# TMC5160_BOB_V1_2.net
KiCad netlist of a schematic drawn in Altium Designer
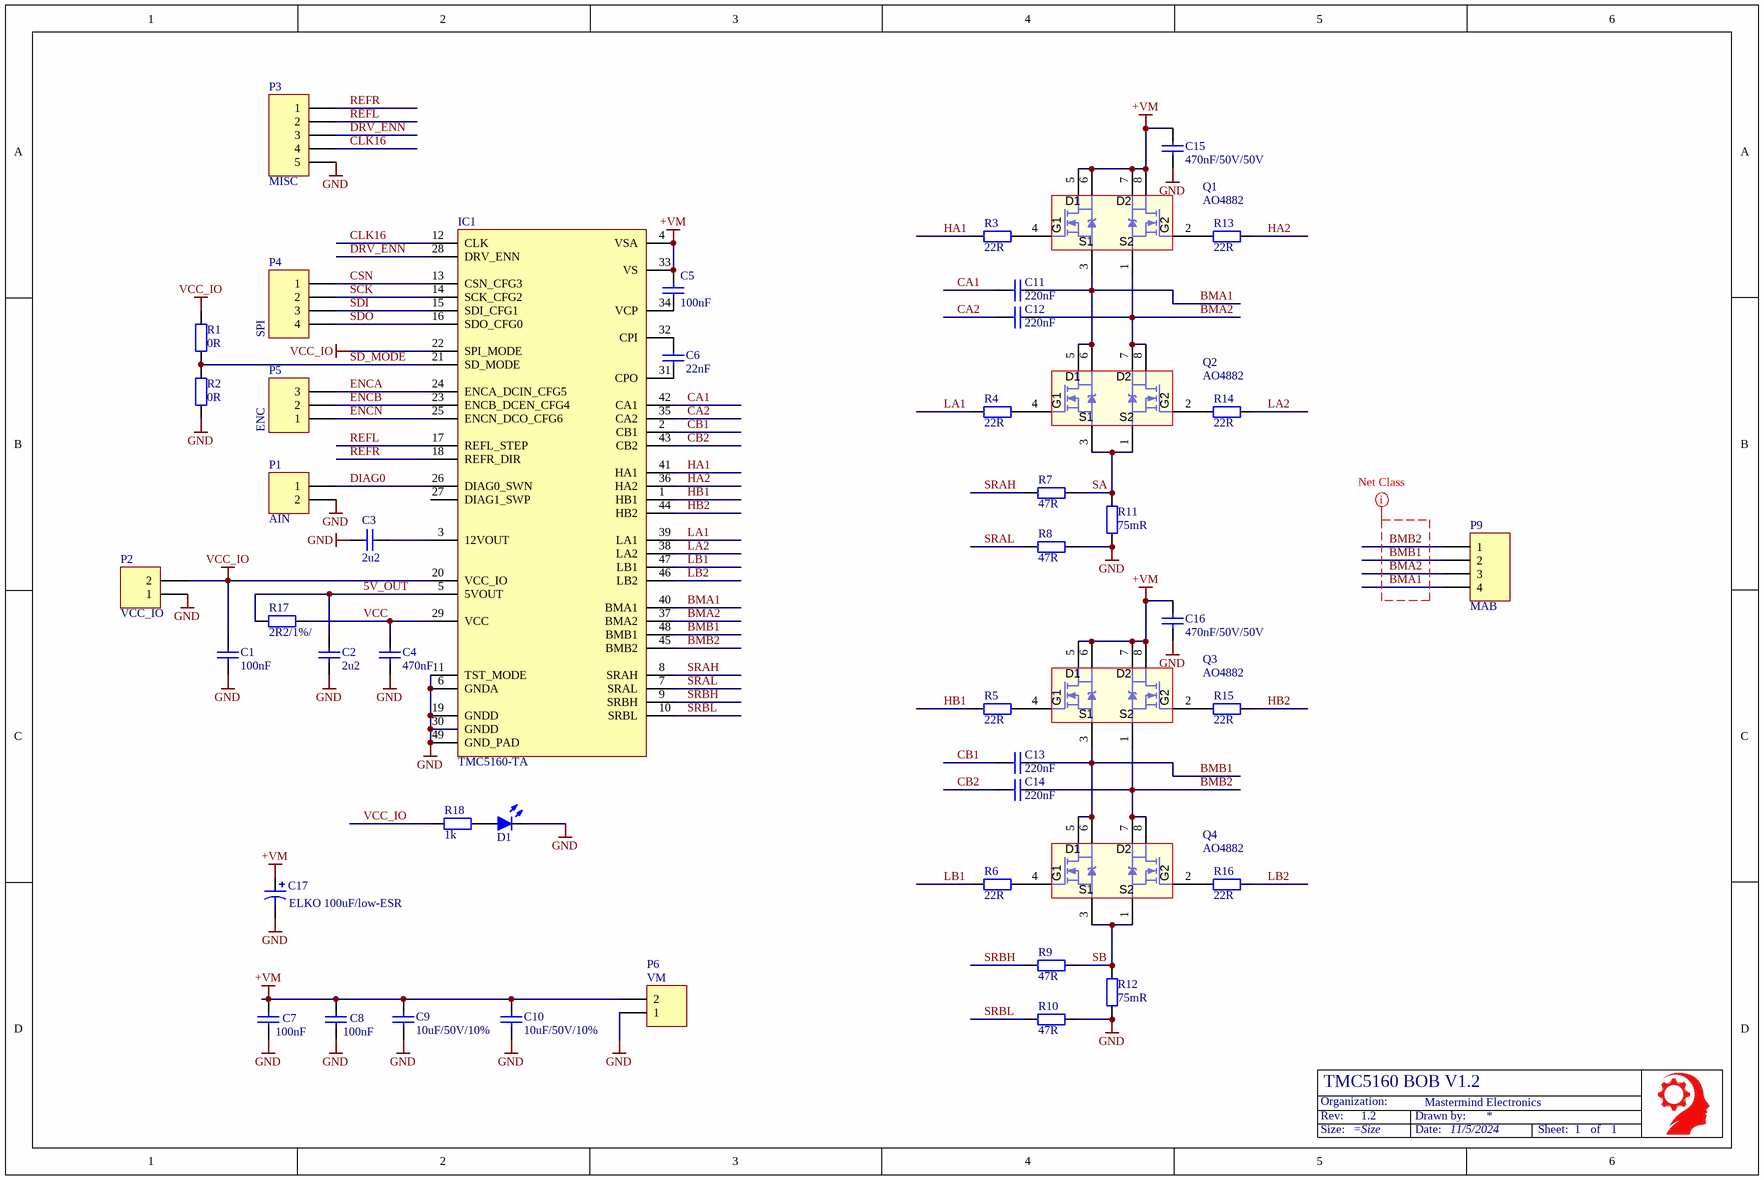
[diagram p0: TMC5160_BOB_V1_2.SchDoc]

(export (version "E")
  (design (tool "Eeschema 10.0.6"))
  (components
    (comp (ref "*")
      (value "TitleBlock")
      (description "Title Block for Schematic Sheets")
      (libsource (lib "mastermind") (part "TitleBlock"))
    )
    (comp (ref "C1")
      (value "100nF")
      (footprint "C0603")
      (description "Ceramic capacitor")
      (fields (field (name "MANUFACTURER") "Multicomp") (field (name "MPN") "MC0603F104M500CT"))
      (libsource (lib "SCH Passives") (part "Capacitor"))
    )
    (comp (ref "C2")
      (value "2u2")
      (footprint "C0603")
      (description "SMD Multilayer Ceramic Capacitor, 0603 [1608 Metric], 2.2 µF, 25 V, ± 10%, X5R, GRM Series")
      (fields (field (name "MF") "MURATA") (field (name "MPN") "GRM188R61E225KA12D"))
      (libsource (lib "TMC5160_RevA") (part "2.2 µF, 25 V, ± 10%, X5R, GRM Series"))
    )
    (comp (ref "C3")
      (value "2u2")
      (footprint "C0603")
      (description "SMD Multilayer Ceramic Capacitor, 0603 [1608 Metric], 2.2 µF, 25 V, ± 10%, X5R, GRM Series")
      (fields (field (name "MF") "MURATA") (field (name "MPN") "GRM188R61E225KA12D"))
      (libsource (lib "TMC5160_RevA") (part "2.2 µF, 25 V, ± 10%, X5R, GRM Series"))
    )
    (comp (ref "C4")
      (value "470nF")
      (footprint "C0603")
      (description "Ceramic capacitor")
      (fields (field (name "MF") "Multicomp") (field (name "MPN") "MC0603X474K160CT"))
      (libsource (lib "SCH Passives") (part "Capacitor"))
    )
    (comp (ref "C5")
      (value "100nF")
      (footprint "C0603")
      (description "Ceramic capacitor")
      (fields (field (name "MF") "Multicomp") (field (name "MPN") "MC0603F104M500CT"))
      (libsource (lib "SCH Passives") (part "Capacitor"))
    )
    (comp (ref "C6")
      (value "22nF")
      (footprint "C0603")
      (description "Ceramic capacitor")
      (fields (field (name "MF") "Multicomp") (field (name "MPN") "MC0603B223K500CT"))
      (libsource (lib "SCH Passives") (part "Capacitor"))
    )
    (comp (ref "C7")
      (value "100nF")
      (footprint "C0603")
      (description "Ceramic capacitor")
      (fields (field (name "MANUFACTURER") "Multicomp") (field (name "MPN") "MC0603F104M500CT"))
      (libsource (lib "SCH Passives") (part "Capacitor"))
    )
    (comp (ref "C8")
      (value "100nF")
      (footprint "C0603")
      (description "Ceramic capacitor")
      (fields (field (name "MANUFACTURER") "Multicomp") (field (name "MPN") "MC0603F104M500CT"))
      (libsource (lib "SCH Passives") (part "Capacitor"))
    )
    (comp (ref "C9")
      (value "10uF/50V/10%")
      (footprint "C1206")
      (description "SMD Multilayer Ceramic Capacitor, 1206 [3216 Metric], 10 µF, 50 V, ± 20%, X5R, GRM Series")
      (fields (field (name "MF") "MURATA") (field (name "MPN") "GRM31CR61H106MA12L"))
      (libsource (lib "TMC262_FDD8424H_RevA") (part "10 µF, 50 V, ± 20%, X5R, GRM Series"))
    )
    (comp (ref "C10")
      (value "10uF/50V/10%")
      (footprint "C1206")
      (description "SMD Multilayer Ceramic Capacitor, 1206 [3216 Metric], 10 µF, 50 V, ± 20%, X5R, GRM Series")
      (fields (field (name "MF") "MURATA") (field (name "MPN") "GRM31CR61H106MA12L"))
      (libsource (lib "TMC262_FDD8424H_RevA") (part "10 µF, 50 V, ± 20%, X5R, GRM Series"))
    )
    (comp (ref "C11")
      (value "220nF")
      (footprint "C0603")
      (description "SMD Multilayer Ceramic Capacitor, 0603 [1608 Metric], 0.22 µF, 50 V, ± 10%, X7R, GCM Series")
      (fields (field (name "MF") "MURATA") (field (name "MPN") "GCM188R71H224KA64D"))
      (libsource (lib "TMC5160_RevA") (part "0.22 µF, 50 V, ± 10%, X7R"))
    )
    (comp (ref "C12")
      (value "220nF")
      (footprint "C0603")
      (description "SMD Multilayer Ceramic Capacitor, 0603 [1608 Metric], 0.22 µF, 50 V, ± 10%, X7R, GCM Series")
      (fields (field (name "MF") "MURATA") (field (name "MPN") "GCM188R71H224KA64D"))
      (libsource (lib "TMC5160_RevA") (part "0.22 µF, 50 V, ± 10%, X7R"))
    )
    (comp (ref "C13")
      (value "220nF")
      (footprint "C0603")
      (description "SMD Multilayer Ceramic Capacitor, 0603 [1608 Metric], 0.22 µF, 50 V, ± 10%, X7R, GCM Series")
      (fields (field (name "MF") "MURATA") (field (name "MPN") "GCM188R71H224KA64D"))
      (libsource (lib "TMC5160_RevA") (part "0.22 µF, 50 V, ± 10%, X7R"))
    )
    (comp (ref "C14")
      (value "220nF")
      (footprint "C0603")
      (description "SMD Multilayer Ceramic Capacitor, 0603 [1608 Metric], 0.22 µF, 50 V, ± 10%, X7R, GCM Series")
      (fields (field (name "MF") "MURATA") (field (name "MPN") "GCM188R71H224KA64D"))
      (libsource (lib "TMC5160_RevA") (part "0.22 µF, 50 V, ± 10%, X7R"))
    )
    (comp (ref "C15")
      (value "470nF/50V/50V")
      (footprint "C0603")
      (description "SMD Multilayer Ceramic Capacitor, 0603 [1608 Metric], 0.47 µF, 50 V, ± 10%, X7R, C Series")
      (fields (field (name "MF") "TDK") (field (name "MPN") "C1608X7R1H474K080AC"))
      (libsource (lib "TMC5160_RevA") (part "0.47 µF, 50 V, ± 10%, X7R, C Series"))
    )
    (comp (ref "C16")
      (value "470nF/50V/50V")
      (footprint "C0603")
      (description "SMD Multilayer Ceramic Capacitor, 0603 [1608 Metric], 0.47 µF, 50 V, ± 10%, X7R, C Series")
      (fields (field (name "MF") "TDK") (field (name "MPN") "C1608X7R1H474K080AC"))
      (libsource (lib "TMC5160_RevA") (part "0.47 µF, 50 V, ± 10%, X7R, C Series"))
    )
    (comp (ref "C17")
      (value "ELKO 100uF/low-ESR")
      (footprint "EXT_POL_CAP")
      (description "Polarized Capacitor (Radial)")
      (fields (field (name "Comment") "Cap Pol1") (field (name "PUBLISHER") "Altium Limited"))
      (libsource (lib "Miscellaneous Devices") (part "Cap Pol1"))
    )
    (comp (ref "D1")
      (value "LED, Blue, SMD, 20mA, 2.8V, 465 nm")
      (footprint "LED_0603")
      (fields (field (name "MF") "Lite-On") (field (name "MPN") "LTST-C191TBKT-5A"))
      (libsource (lib "TMC26x_RevA") (part "LED, Blue, SMD, 20mA, 2.8V, 465 nm"))
    )
    (comp (ref "IC1")
      (value "TMC5160-TA")
      (footprint "TMC5160_TSQFP50P900X900X120_HS-49L")
      (fields (field (name "MANUFACTURER") "TRINAMIC"))
      (libsource (lib "TMC5160_RevA") (part "TMC5160-TA"))
    )
    (comp (ref "P1")
      (value "AIN")
      (footprint "2_PIN_THT")
      (description "Header, 2-Pin")
      (fields (field (name "PUBLISHER") "Altium Limited"))
      (libsource (lib "") (part "Header 2_1"))
    )
    (comp (ref "P2")
      (value "VCC_IO")
      (footprint "2_PIN_THT")
      (description "Header, 2-Pin")
      (fields (field (name "PUBLISHER") "Altium Limited"))
      (libsource (lib "") (part "Header 2_2"))
    )
    (comp (ref "P3")
      (value "MISC")
      (footprint "5_PIN_THT")
      (description "Header, 5-Pin")
      (fields (field (name "PUBLISHER") "Altium Limited"))
      (libsource (lib "Miscellaneous Connectors") (part "Header 5"))
    )
    (comp (ref "P4")
      (value "SPI")
      (footprint "4_PIN_THT")
      (description "Header, 4-Pin")
      (fields (field (name "PUBLISHER") "Altium Limited"))
      (libsource (lib "Miscellaneous Connectors") (part "Header 4"))
    )
    (comp (ref "P5")
      (value "ENC")
      (footprint "3_PIN_THT")
      (description "Header, 3-Pin")
      (fields (field (name "PUBLISHER") "Altium Limited"))
      (libsource (lib "Miscellaneous Connectors") (part "Header 3"))
    )
    (comp (ref "P6")
      (value "VM")
      (footprint "2_PIN_THT")
      (description "Header, 2-Pin")
      (fields (field (name "PUBLISHER") "Altium Limited"))
      (libsource (lib "Miscellaneous Connectors") (part "Header 2"))
    )
    (comp (ref "P9")
      (value "MAB")
      (footprint "4_PIN_THT_1mm_hole")
      (description "Wire-To-Board Connector, 2.5 mm, 4 Contacts, Header, EH Series, Through Hole, 1 Rows")
      (fields (field (name "MPN") "B4B-EH-A") (field (name "MF") "JST (JAPAN SOLDERLESS TERMINALS)"))
      (libsource (lib "TMC5160_RevA") (part "Wire-To-Board Connector, 2.5 mm, 4 Contacts, Header, EH Series, Through Hole, 1 Rows"))
    )
    (comp (ref "Q1")
      (value "AO4882")
      (footprint "SOP127P600X170-8L")
      (description "Mosfet Array 2 N-Channel (Dual) 40V 8A 2W Surface Mount 8-SOIC")
      (fields (field (name "MF") "Alpha & Omega Semiconductor Inc."))
      (libsource (lib "TMC5160_RevA") (part "AO4882 MOSFET 2N-CH 40V 8A 8SOIC"))
    )
    (comp (ref "Q2")
      (value "AO4882")
      (footprint "SOP127P600X170-8L")
      (description "Mosfet Array 2 N-Channel (Dual) 40V 8A 2W Surface Mount 8-SOIC")
      (fields (field (name "MF") "Alpha & Omega Semiconductor Inc."))
      (libsource (lib "TMC5160_RevA") (part "AO4882 MOSFET 2N-CH 40V 8A 8SOIC"))
    )
    (comp (ref "Q3")
      (value "AO4882")
      (footprint "SOP127P600X170-8L")
      (description "Mosfet Array 2 N-Channel (Dual) 40V 8A 2W Surface Mount 8-SOIC")
      (fields (field (name "MF") "Alpha & Omega Semiconductor Inc."))
      (libsource (lib "TMC5160_RevA") (part "AO4882 MOSFET 2N-CH 40V 8A 8SOIC"))
    )
    (comp (ref "Q4")
      (value "AO4882")
      (footprint "SOP127P600X170-8L")
      (description "Mosfet Array 2 N-Channel (Dual) 40V 8A 2W Surface Mount 8-SOIC")
      (fields (field (name "MF") "Alpha & Omega Semiconductor Inc."))
      (libsource (lib "TMC5160_RevA") (part "AO4882 MOSFET 2N-CH 40V 8A 8SOIC"))
    )
    (comp (ref "R1")
      (value "0R")
      (footprint "R0603")
      (description "SMD Chip Resistor, Thick Film, 0 ohm, 0603 [1608 Metric], 100 mW, MCWR Series")
      (fields
        (field (name "MPN") "MCWR06X000 PTL")
        (field (name "MF") "MULTICOMP")
        (field (name "RESISTANCE") "0R")
      )
      (libsource (lib "TMC5160_RevA") (part "0 ohm, 0603 [1608 Metric], 100 mW, MCWR Series"))
    )
    (comp (ref "R2")
      (value "0R")
      (footprint "R0603")
      (description "SMD Chip Resistor, Thick Film, 0 ohm, 0603 [1608 Metric], 100 mW, MCWR Series")
      (fields
        (field (name "MPN") "MCWR06X000 PTL")
        (field (name "MF") "MULTICOMP")
        (field (name "RESISTANCE") "0R")
      )
      (libsource (lib "TMC5160_RevA") (part "0 ohm, 0603 [1608 Metric], 100 mW, MCWR Series"))
    )
    (comp (ref "R3")
      (value "22R / 100mW / 1%")
      (footprint "R0603")
      (description "SMD Chip Resistor, Thick Film, 22 ohm, 50 V, 0603 [1608 Metric], 100 mW, ± 1%, MCWR Series")
      (fields
        (field (name "MPN") "MCWR06X22R0FTLV")
        (field (name "MF") "MULTICOMP")
        (field (name "RESISTANCE") "22R")
      )
      (libsource (lib "TMC5160_RevA") (part "22 ohm, 50 V, 0603 [1608 Metric], 100 mW, ± 1%, MCWR Series"))
    )
    (comp (ref "R4")
      (value "22R / 100mW / 1%")
      (footprint "R0603")
      (description "SMD Chip Resistor, Thick Film, 22 ohm, 50 V, 0603 [1608 Metric], 100 mW, ± 1%, MCWR Series")
      (fields
        (field (name "MPN") "MCWR06X22R0FTLV")
        (field (name "MF") "MULTICOMP")
        (field (name "RESISTANCE") "22R")
      )
      (libsource (lib "TMC5160_RevA") (part "22 ohm, 50 V, 0603 [1608 Metric], 100 mW, ± 1%, MCWR Series"))
    )
    (comp (ref "R5")
      (value "22R / 100mW / 1%")
      (footprint "R0603")
      (description "SMD Chip Resistor, Thick Film, 22 ohm, 50 V, 0603 [1608 Metric], 100 mW, ± 1%, MCWR Series")
      (fields
        (field (name "MPN") "MCWR06X22R0FTLV")
        (field (name "MF") "MULTICOMP")
        (field (name "RESISTANCE") "22R")
      )
      (libsource (lib "TMC5160_RevA") (part "22 ohm, 50 V, 0603 [1608 Metric], 100 mW, ± 1%, MCWR Series"))
    )
    (comp (ref "R6")
      (value "22R / 100mW / 1%")
      (footprint "R0603")
      (description "SMD Chip Resistor, Thick Film, 22 ohm, 50 V, 0603 [1608 Metric], 100 mW, ± 1%, MCWR Series")
      (fields
        (field (name "MPN") "MCWR06X22R0FTLV")
        (field (name "MF") "MULTICOMP")
        (field (name "RESISTANCE") "22R")
      )
      (libsource (lib "TMC5160_RevA") (part "22 ohm, 50 V, 0603 [1608 Metric], 100 mW, ± 1%, MCWR Series"))
    )
    (comp (ref "R7")
      (value "47R /  / 1%")
      (footprint "R0603")
      (description "SMD Chip Resistor, Ceramic, 47 ohm, 75 V, 0603 [1608 Metric], 100 mW, ± 1%, MCSR 06 Series")
      (fields
        (field (name "MPN") "MCSR06X47R0FTL")
        (field (name "MF") "MULTICOMP")
        (field (name "RESISTANCE") "47R")
      )
      (libsource (lib "TMC5160_RevA") (part "47 ohm, 75 V, 0603 [1608 Metric], 100 mW, ± 1%, MCSR 06 Series"))
    )
    (comp (ref "R8")
      (value "47R /  / 1%")
      (footprint "R0603")
      (description "SMD Chip Resistor, Ceramic, 47 ohm, 75 V, 0603 [1608 Metric], 100 mW, ± 1%, MCSR 06 Series")
      (fields
        (field (name "MPN") "MCSR06X47R0FTL")
        (field (name "MF") "MULTICOMP")
        (field (name "RESISTANCE") "47R")
      )
      (libsource (lib "TMC5160_RevA") (part "47 ohm, 75 V, 0603 [1608 Metric], 100 mW, ± 1%, MCSR 06 Series"))
    )
    (comp (ref "R9")
      (value "47R /  / 1%")
      (footprint "R0603")
      (description "SMD Chip Resistor, Ceramic, 47 ohm, 75 V, 0603 [1608 Metric], 100 mW, ± 1%, MCSR 06 Series")
      (fields
        (field (name "MPN") "MCSR06X47R0FTL")
        (field (name "MF") "MULTICOMP")
        (field (name "RESISTANCE") "47R")
      )
      (libsource (lib "TMC5160_RevA") (part "47 ohm, 75 V, 0603 [1608 Metric], 100 mW, ± 1%, MCSR 06 Series"))
    )
    (comp (ref "R10")
      (value "47R /  / 1%")
      (footprint "R0603")
      (description "SMD Chip Resistor, Ceramic, 47 ohm, 75 V, 0603 [1608 Metric], 100 mW, ± 1%, MCSR 06 Series")
      (fields
        (field (name "MPN") "MCSR06X47R0FTL")
        (field (name "MF") "MULTICOMP")
        (field (name "RESISTANCE") "47R")
      )
      (libsource (lib "TMC5160_RevA") (part "47 ohm, 75 V, 0603 [1608 Metric], 100 mW, ± 1%, MCSR 06 Series"))
    )
    (comp (ref "R11")
      (value "75mR")
      (footprint "R1206")
      (description "SMD Chip Resistor, Thick Film, Current Sense Resistors - SMD 1W 0.075ohm 1%")
      (fields
        (field (name "MPN") "ERJ-8BWFR075V")
        (field (name "MF") "Panasonic Electronic Components")
        (field (name "RESISTANCE") "75mR")
      )
      (libsource (lib "SMD_Passives") (part "R_SENS, 0.075 ohm, 1206, 1W, ± 1%, ERJ Series"))
    )
    (comp (ref "R12")
      (value "75mR")
      (footprint "R1206")
      (description "SMD Chip Resistor, Thick Film, Current Sense Resistors - SMD 1W 0.075ohm 1%")
      (fields
        (field (name "MPN") "ERJ-8BWFR075V")
        (field (name "MF") "Panasonic Electronic Components")
        (field (name "RESISTANCE") "75mR")
      )
      (libsource (lib "SMD_Passives") (part "R_SENS, 0.075 ohm, 1206, 1W, ± 1%, ERJ Series"))
    )
    (comp (ref "R13")
      (value "22R / 100mW / 1%")
      (footprint "R0603")
      (description "SMD Chip Resistor, Thick Film, 22 ohm, 50 V, 0603 [1608 Metric], 100 mW, ± 1%, MCWR Series")
      (fields
        (field (name "MPN") "MCWR06X22R0FTLV")
        (field (name "MF") "MULTICOMP")
        (field (name "RESISTANCE") "22R")
      )
      (libsource (lib "TMC5160_RevA") (part "22 ohm, 50 V, 0603 [1608 Metric], 100 mW, ± 1%, MCWR Series"))
    )
    (comp (ref "R14")
      (value "22R / 100mW / 1%")
      (footprint "R0603")
      (description "SMD Chip Resistor, Thick Film, 22 ohm, 50 V, 0603 [1608 Metric], 100 mW, ± 1%, MCWR Series")
      (fields
        (field (name "MPN") "MCWR06X22R0FTLV")
        (field (name "MF") "MULTICOMP")
        (field (name "RESISTANCE") "22R")
      )
      (libsource (lib "TMC5160_RevA") (part "22 ohm, 50 V, 0603 [1608 Metric], 100 mW, ± 1%, MCWR Series"))
    )
    (comp (ref "R15")
      (value "22R / 100mW / 1%")
      (footprint "R0603")
      (description "SMD Chip Resistor, Thick Film, 22 ohm, 50 V, 0603 [1608 Metric], 100 mW, ± 1%, MCWR Series")
      (fields
        (field (name "MPN") "MCWR06X22R0FTLV")
        (field (name "MF") "MULTICOMP")
        (field (name "RESISTANCE") "22R")
      )
      (libsource (lib "TMC5160_RevA") (part "22 ohm, 50 V, 0603 [1608 Metric], 100 mW, ± 1%, MCWR Series"))
    )
    (comp (ref "R16")
      (value "22R / 100mW / 1%")
      (footprint "R0603")
      (description "SMD Chip Resistor, Thick Film, 22 ohm, 50 V, 0603 [1608 Metric], 100 mW, ± 1%, MCWR Series")
      (fields
        (field (name "MPN") "MCWR06X22R0FTLV")
        (field (name "MF") "MULTICOMP")
        (field (name "RESISTANCE") "22R")
      )
      (libsource (lib "TMC5160_RevA") (part "22 ohm, 50 V, 0603 [1608 Metric], 100 mW, ± 1%, MCWR Series"))
    )
    (comp (ref "R17")
      (value "2R2/1%/")
      (footprint "R0603")
      (description "Resistor")
      (fields (field (name "MPN") "MC0063W060312R2") (field (name "MF") "Multicomp"))
      (libsource (lib "SCH Passives") (part "Resistor"))
    )
    (comp (ref "R18")
      (value "1k")
      (footprint "R0603")
      (description "1 kohm, 50 V, 0603 [1608 Metric], 63 mW, ± 1%, MC Series")
      (fields
        (field (name "MPN") "MC0063W060311K")
        (field (name "MF") "MULTICOMP")
        (field (name "RESISTANCE") "1k")
      )
      (libsource (lib "TMC457_RevA") (part "1 kohm, 50 V, 0603 [1608 Metric], 63 mW, ± 1%, MC Series"))
    )
  )
  (nets
    (net (code "1") (name "+VM") (class "Default")
      (node (ref "C10") (pin "2") (pinfunction "2_2") (pintype "passive"))
      (node (ref "C15") (pin "1") (pinfunction "1_1") (pintype "passive"))
      (node (ref "C16") (pin "1") (pinfunction "1_1") (pintype "passive"))
      (node (ref "C17") (pin "1") (pinfunction "1_1") (pintype "passive"))
      (node (ref "C5") (pin "1") (pinfunction "1_1") (pintype "passive"))
      (node (ref "C7") (pin "1") (pinfunction "1_1") (pintype "passive"))
      (node (ref "C8") (pin "1") (pinfunction "1_1") (pintype "passive"))
      (node (ref "C9") (pin "2") (pinfunction "2_2") (pintype "passive"))
      (node (ref "IC1") (pin "33") (pinfunction "VS_33") (pintype "passive"))
      (node (ref "IC1") (pin "4") (pinfunction "VSA_4") (pintype "passive"))
      (node (ref "P6") (pin "2") (pinfunction "2_2") (pintype "passive"))
      (node (ref "Q1") (pin "5") (pinfunction "D1_5") (pintype "passive"))
      (node (ref "Q1") (pin "6") (pinfunction "D1_6") (pintype "passive"))
      (node (ref "Q1") (pin "7") (pinfunction "D2_7") (pintype "passive"))
      (node (ref "Q1") (pin "8") (pinfunction "D2_8") (pintype "passive"))
      (node (ref "Q3") (pin "5") (pinfunction "D1_5") (pintype "passive"))
      (node (ref "Q3") (pin "6") (pinfunction "D1_6") (pintype "passive"))
      (node (ref "Q3") (pin "7") (pinfunction "D2_7") (pintype "passive"))
      (node (ref "Q3") (pin "8") (pinfunction "D2_8") (pintype "passive"))
    )
    (net (code "2") (name "/5V_OUT") (class "Default")
      (node (ref "C2") (pin "1") (pinfunction "1_1") (pintype "passive"))
      (node (ref "IC1") (pin "5") (pinfunction "5VOUT_5") (pintype "passive"))
      (node (ref "R17") (pin "1") (pinfunction "1_1") (pintype "passive"))
    )
    (net (code "3") (name "/BMA1") (class "Default")
      (node (ref "C11") (pin "2") (pinfunction "2_2") (pintype "passive"))
      (node (ref "IC1") (pin "40") (pinfunction "BMA1_40") (pintype "passive"))
      (node (ref "P9") (pin "4") (pinfunction "4_4") (pintype "passive"))
      (node (ref "Q1") (pin "3") (pinfunction "S1_3") (pintype "passive"))
      (node (ref "Q2") (pin "5") (pinfunction "D1_5") (pintype "passive"))
      (node (ref "Q2") (pin "6") (pinfunction "D1_6") (pintype "passive"))
    )
    (net (code "4") (name "/BMA2") (class "Default")
      (node (ref "C12") (pin "2") (pinfunction "2_2") (pintype "passive"))
      (node (ref "IC1") (pin "37") (pinfunction "BMA2_37") (pintype "passive"))
      (node (ref "P9") (pin "3") (pinfunction "3_3") (pintype "passive"))
      (node (ref "Q1") (pin "1") (pinfunction "S2_1") (pintype "passive"))
      (node (ref "Q2") (pin "7") (pinfunction "D2_7") (pintype "passive"))
      (node (ref "Q2") (pin "8") (pinfunction "D2_8") (pintype "passive"))
    )
    (net (code "5") (name "/BMB1") (class "Default")
      (node (ref "C13") (pin "2") (pinfunction "2_2") (pintype "passive"))
      (node (ref "IC1") (pin "48") (pinfunction "BMB1_48") (pintype "passive"))
      (node (ref "P9") (pin "2") (pinfunction "2_2") (pintype "passive"))
      (node (ref "Q3") (pin "3") (pinfunction "S1_3") (pintype "passive"))
      (node (ref "Q4") (pin "5") (pinfunction "D1_5") (pintype "passive"))
      (node (ref "Q4") (pin "6") (pinfunction "D1_6") (pintype "passive"))
    )
    (net (code "6") (name "/BMB2") (class "Default")
      (node (ref "C14") (pin "2") (pinfunction "2_2") (pintype "passive"))
      (node (ref "IC1") (pin "45") (pinfunction "BMB2_45") (pintype "passive"))
      (node (ref "P9") (pin "1") (pinfunction "1_1") (pintype "passive"))
      (node (ref "Q3") (pin "1") (pinfunction "S2_1") (pintype "passive"))
      (node (ref "Q4") (pin "7") (pinfunction "D2_7") (pintype "passive"))
      (node (ref "Q4") (pin "8") (pinfunction "D2_8") (pintype "passive"))
    )
    (net (code "7") (name "/CA1") (class "Default")
      (node (ref "C11") (pin "1") (pinfunction "1_1") (pintype "passive"))
      (node (ref "IC1") (pin "42") (pinfunction "CA1_42") (pintype "passive"))
    )
    (net (code "8") (name "/CA2") (class "Default")
      (node (ref "C12") (pin "1") (pinfunction "1_1") (pintype "passive"))
      (node (ref "IC1") (pin "35") (pinfunction "CA2_35") (pintype "passive"))
    )
    (net (code "9") (name "/CB1") (class "Default")
      (node (ref "C13") (pin "1") (pinfunction "1_1") (pintype "passive"))
      (node (ref "IC1") (pin "2") (pinfunction "CB1_2") (pintype "passive"))
    )
    (net (code "10") (name "/CB2") (class "Default")
      (node (ref "C14") (pin "1") (pinfunction "1_1") (pintype "passive"))
      (node (ref "IC1") (pin "43") (pinfunction "CB2_43") (pintype "passive"))
    )
    (net (code "11") (name "/CLK16") (class "Default")
      (node (ref "IC1") (pin "12") (pinfunction "CLK_12") (pintype "passive"))
      (node (ref "P3") (pin "4") (pinfunction "4_4") (pintype "passive"))
    )
    (net (code "12") (name "/CSN") (class "Default")
      (node (ref "IC1") (pin "13") (pinfunction "CSN_CFG3_13") (pintype "passive"))
      (node (ref "P4") (pin "1") (pinfunction "1_1") (pintype "passive"))
    )
    (net (code "13") (name "/DIAG0") (class "Default")
      (node (ref "IC1") (pin "26") (pinfunction "DIAG0_SWN_26") (pintype "passive"))
      (node (ref "P1") (pin "1") (pinfunction "1_1") (pintype "passive"))
    )
    (net (code "14") (name "/DRV_ENN") (class "Default")
      (node (ref "IC1") (pin "28") (pinfunction "DRV_ENN_28") (pintype "passive"))
      (node (ref "P3") (pin "3") (pinfunction "3_3") (pintype "passive"))
    )
    (net (code "15") (name "/ENCA") (class "Default")
      (node (ref "IC1") (pin "24") (pinfunction "ENCA_DCIN_CFG5_24") (pintype "passive"))
      (node (ref "P5") (pin "3") (pinfunction "3_3") (pintype "passive"))
    )
    (net (code "16") (name "/ENCB") (class "Default")
      (node (ref "IC1") (pin "23") (pinfunction "ENCB_DCEN_CFG4_23") (pintype "passive"))
      (node (ref "P5") (pin "2") (pinfunction "2_2") (pintype "passive"))
    )
    (net (code "17") (name "/ENCN") (class "Default")
      (node (ref "IC1") (pin "25") (pinfunction "ENCN_DCO_CFG6_25") (pintype "passive"))
      (node (ref "P5") (pin "1") (pinfunction "1_1") (pintype "passive"))
    )
    (net (code "18") (name "/HA1") (class "Default")
      (node (ref "IC1") (pin "41") (pinfunction "HA1_41") (pintype "passive"))
      (node (ref "R3") (pin "2") (pinfunction "2_2") (pintype "passive"))
    )
    (net (code "19") (name "/HA2") (class "Default")
      (node (ref "IC1") (pin "36") (pinfunction "HA2_36") (pintype "passive"))
      (node (ref "R13") (pin "1") (pinfunction "1_1") (pintype "passive"))
    )
    (net (code "20") (name "/HB1") (class "Default")
      (node (ref "IC1") (pin "1") (pinfunction "HB1_1") (pintype "passive"))
      (node (ref "R5") (pin "2") (pinfunction "2_2") (pintype "passive"))
    )
    (net (code "21") (name "/HB2") (class "Default")
      (node (ref "IC1") (pin "44") (pinfunction "HB2_44") (pintype "passive"))
      (node (ref "R15") (pin "1") (pinfunction "1_1") (pintype "passive"))
    )
    (net (code "22") (name "/LA1") (class "Default")
      (node (ref "IC1") (pin "39") (pinfunction "LA1_39") (pintype "passive"))
      (node (ref "R4") (pin "2") (pinfunction "2_2") (pintype "passive"))
    )
    (net (code "23") (name "/LA2") (class "Default")
      (node (ref "IC1") (pin "38") (pinfunction "LA2_38") (pintype "passive"))
      (node (ref "R14") (pin "1") (pinfunction "1_1") (pintype "passive"))
    )
    (net (code "24") (name "/LB1") (class "Default")
      (node (ref "IC1") (pin "47") (pinfunction "LB1_47") (pintype "passive"))
      (node (ref "R6") (pin "2") (pinfunction "2_2") (pintype "passive"))
    )
    (net (code "25") (name "/LB2") (class "Default")
      (node (ref "IC1") (pin "46") (pinfunction "LB2_46") (pintype "passive"))
      (node (ref "R16") (pin "1") (pinfunction "1_1") (pintype "passive"))
    )
    (net (code "26") (name "/REFL") (class "Default")
      (node (ref "IC1") (pin "17") (pinfunction "REFL_STEP_17") (pintype "passive"))
      (node (ref "P3") (pin "2") (pinfunction "2_2") (pintype "passive"))
    )
    (net (code "27") (name "/REFR") (class "Default")
      (node (ref "IC1") (pin "18") (pinfunction "REFR_DIR_18") (pintype "passive"))
      (node (ref "P3") (pin "1") (pinfunction "1_1") (pintype "passive"))
    )
    (net (code "28") (name "/SA") (class "Default")
      (node (ref "Q2") (pin "1") (pinfunction "S2_1") (pintype "passive"))
      (node (ref "Q2") (pin "3") (pinfunction "S1_3") (pintype "passive"))
      (node (ref "R11") (pin "1") (pinfunction "1_1") (pintype "passive"))
      (node (ref "R7") (pin "1") (pinfunction "1_1") (pintype "passive"))
    )
    (net (code "29") (name "/SB") (class "Default")
      (node (ref "Q4") (pin "1") (pinfunction "S2_1") (pintype "passive"))
      (node (ref "Q4") (pin "3") (pinfunction "S1_3") (pintype "passive"))
      (node (ref "R12") (pin "1") (pinfunction "1_1") (pintype "passive"))
      (node (ref "R9") (pin "1") (pinfunction "1_1") (pintype "passive"))
    )
    (net (code "30") (name "/SCK") (class "Default")
      (node (ref "IC1") (pin "14") (pinfunction "SCK_CFG2_14") (pintype "passive"))
      (node (ref "P4") (pin "2") (pinfunction "2_2") (pintype "passive"))
    )
    (net (code "31") (name "/SDI") (class "Default")
      (node (ref "IC1") (pin "15") (pinfunction "SDI_CFG1_15") (pintype "passive"))
      (node (ref "P4") (pin "3") (pinfunction "3_3") (pintype "passive"))
    )
    (net (code "32") (name "/SDO") (class "Default")
      (node (ref "IC1") (pin "16") (pinfunction "SDO_CFG0_16") (pintype "passive"))
      (node (ref "P4") (pin "4") (pinfunction "4_4") (pintype "passive"))
    )
    (net (code "33") (name "/SD_MODE") (class "Default")
      (node (ref "IC1") (pin "21") (pinfunction "SD_MODE_21") (pintype "passive"))
      (node (ref "R1") (pin "2") (pinfunction "2_2") (pintype "passive"))
      (node (ref "R2") (pin "1") (pinfunction "1_1") (pintype "passive"))
    )
    (net (code "34") (name "/SRAH") (class "Default")
      (node (ref "IC1") (pin "8") (pinfunction "SRAH_8") (pintype "passive"))
      (node (ref "R7") (pin "2") (pinfunction "2_2") (pintype "passive"))
    )
    (net (code "35") (name "/SRAL") (class "Default")
      (node (ref "IC1") (pin "7") (pinfunction "SRAL_7") (pintype "passive"))
      (node (ref "R8") (pin "2") (pinfunction "2_2") (pintype "passive"))
    )
    (net (code "36") (name "/SRBH") (class "Default")
      (node (ref "IC1") (pin "9") (pinfunction "SRBH_9") (pintype "passive"))
      (node (ref "R9") (pin "2") (pinfunction "2_2") (pintype "passive"))
    )
    (net (code "37") (name "/SRBL") (class "Default")
      (node (ref "IC1") (pin "10") (pinfunction "SRBL_10") (pintype "passive"))
      (node (ref "R10") (pin "2") (pinfunction "2_2") (pintype "passive"))
    )
    (net (code "38") (name "/VCC") (class "Default")
      (node (ref "C4") (pin "1") (pinfunction "1_1") (pintype "passive"))
      (node (ref "IC1") (pin "29") (pinfunction "VCC_29") (pintype "passive"))
      (node (ref "R17") (pin "2") (pinfunction "2_2") (pintype "passive"))
    )
    (net (code "39") (name "GND") (class "Default")
      (node (ref "C1") (pin "2") (pinfunction "2_2") (pintype "passive"))
      (node (ref "C10") (pin "1") (pinfunction "1_1") (pintype "passive"))
      (node (ref "C15") (pin "2") (pinfunction "2_2") (pintype "passive"))
      (node (ref "C16") (pin "2") (pinfunction "2_2") (pintype "passive"))
      (node (ref "C17") (pin "2") (pinfunction "2_2") (pintype "passive"))
      (node (ref "C2") (pin "2") (pinfunction "2_2") (pintype "passive"))
      (node (ref "C3") (pin "1") (pinfunction "1_1") (pintype "passive"))
      (node (ref "C4") (pin "2") (pinfunction "2_2") (pintype "passive"))
      (node (ref "C7") (pin "2") (pinfunction "2_2") (pintype "passive"))
      (node (ref "C8") (pin "2") (pinfunction "2_2") (pintype "passive"))
      (node (ref "C9") (pin "1") (pinfunction "1_1") (pintype "passive"))
      (node (ref "D1") (pin "2") (pinfunction "K_2") (pintype "passive"))
      (node (ref "IC1") (pin "11") (pinfunction "TST_MODE_11") (pintype "passive"))
      (node (ref "IC1") (pin "19") (pinfunction "GNDD_19") (pintype "passive"))
      (node (ref "IC1") (pin "30") (pinfunction "GNDD_30") (pintype "passive"))
      (node (ref "IC1") (pin "49") (pinfunction "GND_PAD_49") (pintype "passive"))
      (node (ref "IC1") (pin "6") (pinfunction "GNDA_6") (pintype "passive"))
      (node (ref "P1") (pin "2") (pinfunction "2_2") (pintype "passive"))
      (node (ref "P2") (pin "1") (pinfunction "1_1") (pintype "passive"))
      (node (ref "P3") (pin "5") (pinfunction "5_5") (pintype "passive"))
      (node (ref "P6") (pin "1") (pinfunction "1_1") (pintype "passive"))
      (node (ref "R10") (pin "1") (pinfunction "1_1") (pintype "passive"))
      (node (ref "R11") (pin "2") (pinfunction "2_2") (pintype "passive"))
      (node (ref "R12") (pin "2") (pinfunction "2_2") (pintype "passive"))
      (node (ref "R2") (pin "2") (pinfunction "2_2") (pintype "passive"))
      (node (ref "R8") (pin "1") (pinfunction "1_1") (pintype "passive"))
    )
    (net (code "40") (name "Net-(D1-A)") (class "Default")
      (node (ref "D1") (pin "1") (pinfunction "A_1") (pintype "passive"))
      (node (ref "R18") (pin "2") (pinfunction "2_2") (pintype "passive"))
    )
    (net (code "41") (name "Net-(IC1-12VOUT)") (class "Default")
      (node (ref "C3") (pin "2") (pinfunction "2_2") (pintype "passive"))
      (node (ref "IC1") (pin "3") (pinfunction "12VOUT_3") (pintype "passive"))
    )
    (net (code "42") (name "Net-(IC1-CPI)") (class "Default")
      (node (ref "C6") (pin "2") (pinfunction "2_2") (pintype "passive"))
      (node (ref "IC1") (pin "32") (pinfunction "CPI_32") (pintype "passive"))
    )
    (net (code "43") (name "Net-(IC1-CPO)") (class "Default")
      (node (ref "C6") (pin "1") (pinfunction "1_1") (pintype "passive"))
      (node (ref "IC1") (pin "31") (pinfunction "CPO_31") (pintype "passive"))
    )
    (net (code "44") (name "Net-(IC1-VCP)") (class "Default")
      (node (ref "C5") (pin "2") (pinfunction "2_2") (pintype "passive"))
      (node (ref "IC1") (pin "34") (pinfunction "VCP_34") (pintype "passive"))
    )
    (net (code "45") (name "Net-(Q1-G1)") (class "Default")
      (node (ref "Q1") (pin "4") (pinfunction "G1_4") (pintype "passive"))
      (node (ref "R3") (pin "1") (pinfunction "1_1") (pintype "passive"))
    )
    (net (code "46") (name "Net-(Q1-G2)") (class "Default")
      (node (ref "Q1") (pin "2") (pinfunction "G2_2") (pintype "passive"))
      (node (ref "R13") (pin "2") (pinfunction "2_2") (pintype "passive"))
    )
    (net (code "47") (name "Net-(Q2-G1)") (class "Default")
      (node (ref "Q2") (pin "4") (pinfunction "G1_4") (pintype "passive"))
      (node (ref "R4") (pin "1") (pinfunction "1_1") (pintype "passive"))
    )
    (net (code "48") (name "Net-(Q2-G2)") (class "Default")
      (node (ref "Q2") (pin "2") (pinfunction "G2_2") (pintype "passive"))
      (node (ref "R14") (pin "2") (pinfunction "2_2") (pintype "passive"))
    )
    (net (code "49") (name "Net-(Q3-G1)") (class "Default")
      (node (ref "Q3") (pin "4") (pinfunction "G1_4") (pintype "passive"))
      (node (ref "R5") (pin "1") (pinfunction "1_1") (pintype "passive"))
    )
    (net (code "50") (name "Net-(Q3-G2)") (class "Default")
      (node (ref "Q3") (pin "2") (pinfunction "G2_2") (pintype "passive"))
      (node (ref "R15") (pin "2") (pinfunction "2_2") (pintype "passive"))
    )
    (net (code "51") (name "Net-(Q4-G1)") (class "Default")
      (node (ref "Q4") (pin "4") (pinfunction "G1_4") (pintype "passive"))
      (node (ref "R6") (pin "1") (pinfunction "1_1") (pintype "passive"))
    )
    (net (code "52") (name "Net-(Q4-G2)") (class "Default")
      (node (ref "Q4") (pin "2") (pinfunction "G2_2") (pintype "passive"))
      (node (ref "R16") (pin "2") (pinfunction "2_2") (pintype "passive"))
    )
    (net (code "53") (name "VCC_IO") (class "Default")
      (node (ref "C1") (pin "1") (pinfunction "1_1") (pintype "passive"))
      (node (ref "IC1") (pin "20") (pinfunction "VCC_IO_20") (pintype "passive"))
      (node (ref "IC1") (pin "22") (pinfunction "SPI_MODE_22") (pintype "passive"))
      (node (ref "P2") (pin "2") (pinfunction "2_2") (pintype "passive"))
      (node (ref "R1") (pin "1") (pinfunction "1_1") (pintype "passive"))
      (node (ref "R18") (pin "1") (pinfunction "1_1") (pintype "passive"))
    )
    (net (code "54") (name "unconnected-(IC1-DIAG1_SWP-Pad27)") (class "Default")
      (node (ref "IC1") (pin "27") (pinfunction "DIAG1_SWP_27") (pintype "passive"))
    )
  )
)
